# main_schematic.net
KiCad netlist of a schematic drawn in Altium Designer
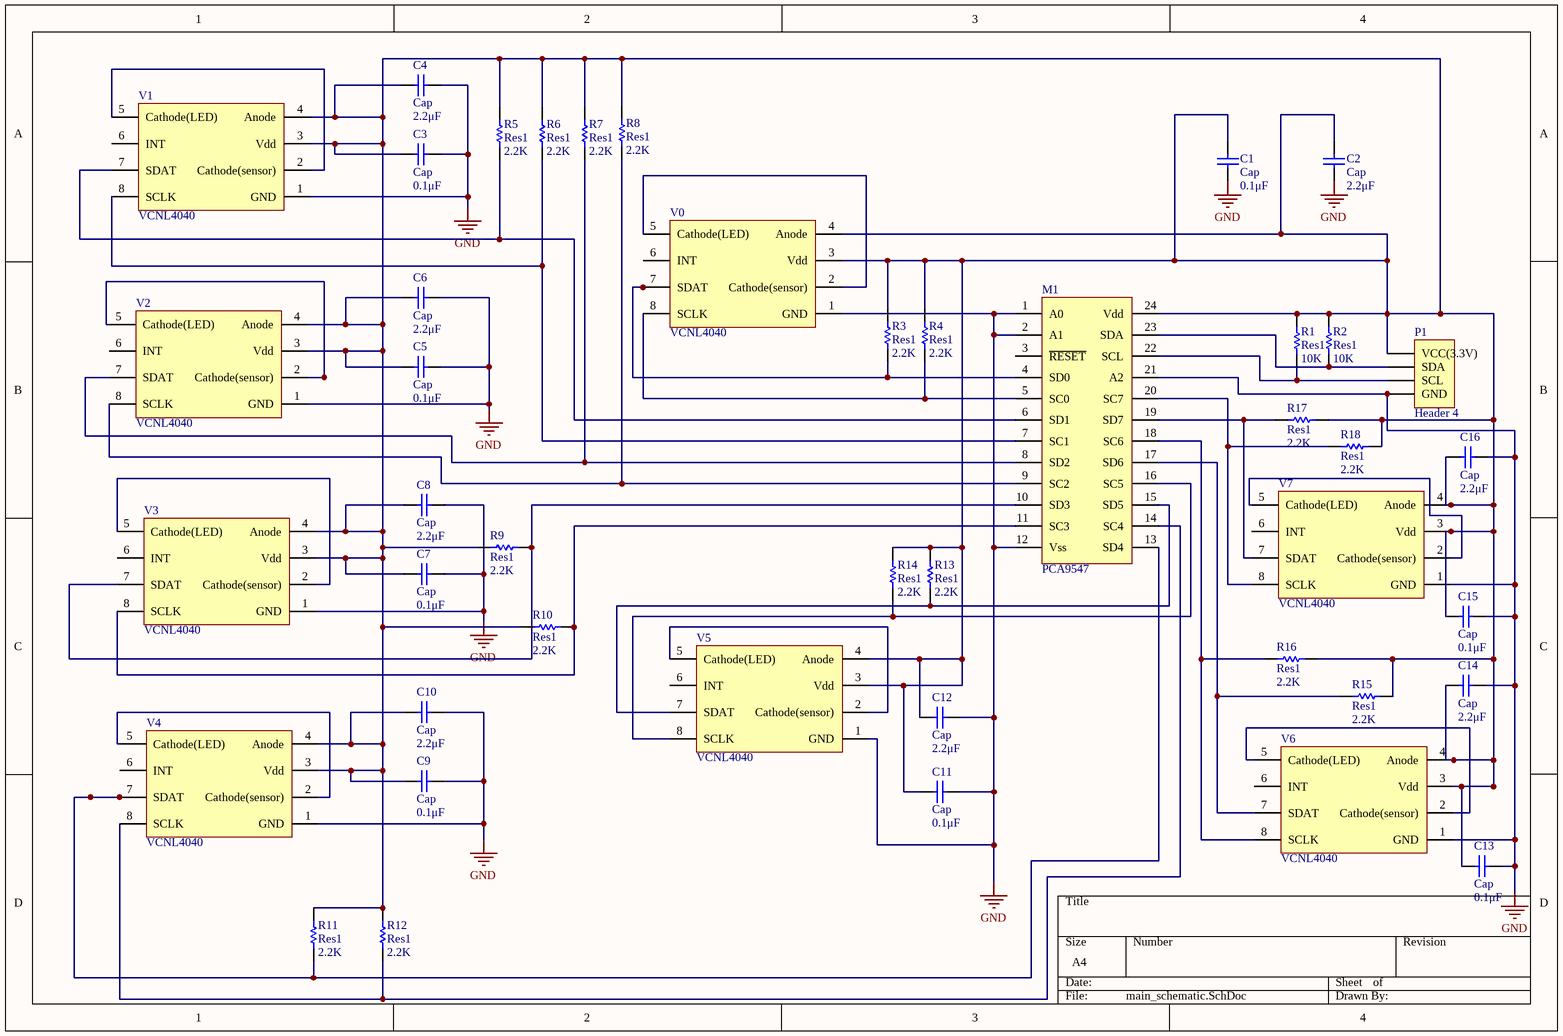
[diagram p0: main_schematic.SchDoc]

(export (version "E")
  (design (tool "Eeschema 10.0.6"))
  (components
    (comp (ref "C1")
      (value "Cap")
      (footprint "1608[0603]")
      (description "Capacitor")
      (fields (field (name "ALTIUM_VALUE") "0.1μF") (field (name "PUBLISHER") "Altium Limited"))
      (libsource (lib "Miscellaneous Devices") (part "Cap"))
    )
    (comp (ref "C2")
      (value "Cap")
      (footprint "1608[0603]")
      (description "Capacitor")
      (fields (field (name "ALTIUM_VALUE") "2.2μF") (field (name "PUBLISHER") "Altium Limited"))
      (libsource (lib "Miscellaneous Devices") (part "Cap"))
    )
    (comp (ref "C3")
      (value "Cap")
      (footprint "1608[0603]")
      (description "Capacitor")
      (fields (field (name "ALTIUM_VALUE") "0.1μF") (field (name "PUBLISHER") "Altium Limited"))
      (libsource (lib "Miscellaneous Devices") (part "Cap"))
    )
    (comp (ref "C4")
      (value "Cap")
      (footprint "1608[0603]")
      (description "Capacitor")
      (fields (field (name "ALTIUM_VALUE") "2.2μF") (field (name "PUBLISHER") "Altium Limited"))
      (libsource (lib "Miscellaneous Devices") (part "Cap"))
    )
    (comp (ref "C5")
      (value "Cap")
      (footprint "1608[0603]")
      (description "Capacitor")
      (fields (field (name "ALTIUM_VALUE") "0.1μF") (field (name "PUBLISHER") "Altium Limited"))
      (libsource (lib "Miscellaneous Devices") (part "Cap"))
    )
    (comp (ref "C6")
      (value "Cap")
      (footprint "1608[0603]")
      (description "Capacitor")
      (fields (field (name "ALTIUM_VALUE") "2.2μF") (field (name "PUBLISHER") "Altium Limited"))
      (libsource (lib "Miscellaneous Devices") (part "Cap"))
    )
    (comp (ref "C7")
      (value "Cap")
      (footprint "1608[0603]")
      (description "Capacitor")
      (fields (field (name "ALTIUM_VALUE") "0.1μF") (field (name "PUBLISHER") "Altium Limited"))
      (libsource (lib "Miscellaneous Devices") (part "Cap"))
    )
    (comp (ref "C8")
      (value "Cap")
      (footprint "1608[0603]")
      (description "Capacitor")
      (fields (field (name "ALTIUM_VALUE") "2.2μF") (field (name "PUBLISHER") "Altium Limited"))
      (libsource (lib "Miscellaneous Devices") (part "Cap"))
    )
    (comp (ref "C9")
      (value "Cap")
      (footprint "1608[0603]")
      (description "Capacitor")
      (fields (field (name "ALTIUM_VALUE") "0.1μF") (field (name "PUBLISHER") "Altium Limited"))
      (libsource (lib "Miscellaneous Devices") (part "Cap"))
    )
    (comp (ref "C10")
      (value "Cap")
      (footprint "1608[0603]")
      (description "Capacitor")
      (fields (field (name "ALTIUM_VALUE") "2.2μF") (field (name "PUBLISHER") "Altium Limited"))
      (libsource (lib "Miscellaneous Devices") (part "Cap"))
    )
    (comp (ref "C11")
      (value "Cap")
      (footprint "1608[0603]")
      (description "Capacitor")
      (fields (field (name "ALTIUM_VALUE") "0.1μF") (field (name "PUBLISHER") "Altium Limited"))
      (libsource (lib "Miscellaneous Devices") (part "Cap"))
    )
    (comp (ref "C12")
      (value "Cap")
      (footprint "1608[0603]")
      (description "Capacitor")
      (fields (field (name "ALTIUM_VALUE") "2.2μF") (field (name "PUBLISHER") "Altium Limited"))
      (libsource (lib "Miscellaneous Devices") (part "Cap"))
    )
    (comp (ref "C13")
      (value "Cap")
      (footprint "1608[0603]")
      (description "Capacitor")
      (fields (field (name "ALTIUM_VALUE") "0.1μF") (field (name "PUBLISHER") "Altium Limited"))
      (libsource (lib "Miscellaneous Devices") (part "Cap"))
    )
    (comp (ref "C14")
      (value "Cap")
      (footprint "1608[0603]")
      (description "Capacitor")
      (fields (field (name "ALTIUM_VALUE") "2.2μF") (field (name "PUBLISHER") "Altium Limited"))
      (libsource (lib "Miscellaneous Devices") (part "Cap"))
    )
    (comp (ref "C15")
      (value "Cap")
      (footprint "1608[0603]")
      (description "Capacitor")
      (fields (field (name "ALTIUM_VALUE") "0.1μF") (field (name "PUBLISHER") "Altium Limited"))
      (libsource (lib "Miscellaneous Devices") (part "Cap"))
    )
    (comp (ref "C16")
      (value "Cap")
      (footprint "1608[0603]")
      (description "Capacitor")
      (fields (field (name "ALTIUM_VALUE") "2.2μF") (field (name "PUBLISHER") "Altium Limited"))
      (libsource (lib "Miscellaneous Devices") (part "Cap"))
    )
    (comp (ref "M1") (value "PCA9547") (footprint "TSSOP24") (libsource (lib "PCA9547") (part "PCA9547")))
    (comp (ref "P1")
      (value "Header 4")
      (footprint "HDR1X4")
      (description "Header, 4-Pin")
      (fields (field (name "PUBLISHER") "Altium Limited"))
      (libsource (lib "Miscellaneous Connectors") (part "Header 4"))
    )
    (comp (ref "R1")
      (value "Res1")
      (footprint "1608[0603]")
      (description "Resistor")
      (fields (field (name "ALTIUM_VALUE") "10K") (field (name "PUBLISHER") "Altium Limited"))
      (libsource (lib "Miscellaneous Devices") (part "Res1"))
    )
    (comp (ref "R2")
      (value "Res1")
      (footprint "1608[0603]")
      (description "Resistor")
      (fields (field (name "ALTIUM_VALUE") "10K") (field (name "PUBLISHER") "Altium Limited"))
      (libsource (lib "Miscellaneous Devices") (part "Res1"))
    )
    (comp (ref "R3")
      (value "Res1")
      (footprint "1608[0603]")
      (description "Resistor")
      (fields (field (name "ALTIUM_VALUE") "2.2K") (field (name "PUBLISHER") "Altium Limited"))
      (libsource (lib "Miscellaneous Devices") (part "Res1"))
    )
    (comp (ref "R4")
      (value "Res1")
      (footprint "1608[0603]")
      (description "Resistor")
      (fields (field (name "ALTIUM_VALUE") "2.2K") (field (name "PUBLISHER") "Altium Limited"))
      (libsource (lib "Miscellaneous Devices") (part "Res1"))
    )
    (comp (ref "R5")
      (value "Res1")
      (footprint "1608[0603]")
      (description "Resistor")
      (fields (field (name "ALTIUM_VALUE") "2.2K") (field (name "PUBLISHER") "Altium Limited"))
      (libsource (lib "Miscellaneous Devices") (part "Res1"))
    )
    (comp (ref "R6")
      (value "Res1")
      (footprint "1608[0603]")
      (description "Resistor")
      (fields (field (name "ALTIUM_VALUE") "2.2K") (field (name "PUBLISHER") "Altium Limited"))
      (libsource (lib "Miscellaneous Devices") (part "Res1"))
    )
    (comp (ref "R7")
      (value "Res1")
      (footprint "1608[0603]")
      (description "Resistor")
      (fields (field (name "ALTIUM_VALUE") "2.2K") (field (name "PUBLISHER") "Altium Limited"))
      (libsource (lib "Miscellaneous Devices") (part "Res1"))
    )
    (comp (ref "R8")
      (value "Res1")
      (footprint "1608[0603]")
      (description "Resistor")
      (fields (field (name "ALTIUM_VALUE") "2.2K") (field (name "PUBLISHER") "Altium Limited"))
      (libsource (lib "Miscellaneous Devices") (part "Res1"))
    )
    (comp (ref "R9")
      (value "Res1")
      (footprint "1608[0603]")
      (description "Resistor")
      (fields (field (name "ALTIUM_VALUE") "2.2K") (field (name "PUBLISHER") "Altium Limited"))
      (libsource (lib "Miscellaneous Devices") (part "Res1"))
    )
    (comp (ref "R10")
      (value "Res1")
      (footprint "1608[0603]")
      (description "Resistor")
      (fields (field (name "ALTIUM_VALUE") "2.2K") (field (name "PUBLISHER") "Altium Limited"))
      (libsource (lib "Miscellaneous Devices") (part "Res1"))
    )
    (comp (ref "R11")
      (value "Res1")
      (footprint "1608[0603]")
      (description "Resistor")
      (fields (field (name "ALTIUM_VALUE") "2.2K") (field (name "PUBLISHER") "Altium Limited"))
      (libsource (lib "Miscellaneous Devices") (part "Res1"))
    )
    (comp (ref "R12")
      (value "Res1")
      (footprint "1608[0603]")
      (description "Resistor")
      (fields (field (name "ALTIUM_VALUE") "2.2K") (field (name "PUBLISHER") "Altium Limited"))
      (libsource (lib "Miscellaneous Devices") (part "Res1"))
    )
    (comp (ref "R13")
      (value "Res1")
      (footprint "1608[0603]")
      (description "Resistor")
      (fields (field (name "ALTIUM_VALUE") "2.2K") (field (name "PUBLISHER") "Altium Limited"))
      (libsource (lib "Miscellaneous Devices") (part "Res1"))
    )
    (comp (ref "R14")
      (value "Res1")
      (footprint "1608[0603]")
      (description "Resistor")
      (fields (field (name "ALTIUM_VALUE") "2.2K") (field (name "PUBLISHER") "Altium Limited"))
      (libsource (lib "Miscellaneous Devices") (part "Res1"))
    )
    (comp (ref "R15")
      (value "Res1")
      (footprint "1608[0603]")
      (description "Resistor")
      (fields (field (name "ALTIUM_VALUE") "2.2K") (field (name "PUBLISHER") "Altium Limited"))
      (libsource (lib "Miscellaneous Devices") (part "Res1"))
    )
    (comp (ref "R16")
      (value "Res1")
      (footprint "1608[0603]")
      (description "Resistor")
      (fields (field (name "ALTIUM_VALUE") "2.2K") (field (name "PUBLISHER") "Altium Limited"))
      (libsource (lib "Miscellaneous Devices") (part "Res1"))
    )
    (comp (ref "R17")
      (value "Res1")
      (footprint "1608[0603]")
      (description "Resistor")
      (fields (field (name "ALTIUM_VALUE") "2.2K") (field (name "PUBLISHER") "Altium Limited"))
      (libsource (lib "Miscellaneous Devices") (part "Res1"))
    )
    (comp (ref "R18")
      (value "Res1")
      (footprint "1608[0603]")
      (description "Resistor")
      (fields (field (name "ALTIUM_VALUE") "2.2K") (field (name "PUBLISHER") "Altium Limited"))
      (libsource (lib "Miscellaneous Devices") (part "Res1"))
    )
    (comp (ref "V0") (value "VCNL4040") (footprint "SOP8") (libsource (lib "VCNL4040") (part "Component_1")))
    (comp (ref "V1") (value "VCNL4040") (footprint "SOP8") (libsource (lib "VCNL4040") (part "Component_1")))
    (comp (ref "V2") (value "VCNL4040") (footprint "SOP8") (libsource (lib "VCNL4040") (part "Component_1")))
    (comp (ref "V3") (value "VCNL4040") (footprint "SOP8") (libsource (lib "VCNL4040") (part "Component_1")))
    (comp (ref "V4") (value "VCNL4040") (footprint "SOP8") (libsource (lib "VCNL4040") (part "Component_1")))
    (comp (ref "V5") (value "VCNL4040") (footprint "SOP8") (libsource (lib "VCNL4040") (part "Component_1")))
    (comp (ref "V6") (value "VCNL4040") (footprint "SOP8") (libsource (lib "VCNL4040") (part "Component_1")))
    (comp (ref "V7") (value "VCNL4040") (footprint "SOP8") (libsource (lib "VCNL4040") (part "Component_1")))
  )
  (nets
    (net (code "1") (name "GND") (class "Default")
      (node (ref "C1") (pin "1") (pinfunction "1_1") (pintype "passive"))
      (node (ref "C10") (pin "1") (pinfunction "1_1") (pintype "passive"))
      (node (ref "C11") (pin "1") (pinfunction "1_1") (pintype "passive"))
      (node (ref "C12") (pin "1") (pinfunction "1_1") (pintype "passive"))
      (node (ref "C13") (pin "1") (pinfunction "1_1") (pintype "passive"))
      (node (ref "C14") (pin "1") (pinfunction "1_1") (pintype "passive"))
      (node (ref "C15") (pin "1") (pinfunction "1_1") (pintype "passive"))
      (node (ref "C16") (pin "1") (pinfunction "1_1") (pintype "passive"))
      (node (ref "C2") (pin "1") (pinfunction "1_1") (pintype "passive"))
      (node (ref "C3") (pin "1") (pinfunction "1_1") (pintype "passive"))
      (node (ref "C4") (pin "1") (pinfunction "1_1") (pintype "passive"))
      (node (ref "C5") (pin "1") (pinfunction "1_1") (pintype "passive"))
      (node (ref "C6") (pin "1") (pinfunction "1_1") (pintype "passive"))
      (node (ref "C7") (pin "1") (pinfunction "1_1") (pintype "passive"))
      (node (ref "C8") (pin "1") (pinfunction "1_1") (pintype "passive"))
      (node (ref "C9") (pin "1") (pinfunction "1_1") (pintype "passive"))
      (node (ref "M1") (pin "1") (pinfunction "A0_1") (pintype "passive"))
      (node (ref "M1") (pin "12") (pinfunction "Vss_12") (pintype "passive"))
      (node (ref "M1") (pin "2") (pinfunction "A1_2") (pintype "passive"))
      (node (ref "M1") (pin "21") (pinfunction "A2_21") (pintype "passive"))
      (node (ref "P1") (pin "4") (pinfunction "GND_4") (pintype "power_in"))
      (node (ref "V0") (pin "1") (pinfunction "GND_1") (pintype "passive"))
      (node (ref "V1") (pin "1") (pinfunction "GND_1") (pintype "passive"))
      (node (ref "V2") (pin "1") (pinfunction "GND_1") (pintype "passive"))
      (node (ref "V3") (pin "1") (pinfunction "GND_1") (pintype "passive"))
      (node (ref "V4") (pin "1") (pinfunction "GND_1") (pintype "passive"))
      (node (ref "V5") (pin "1") (pinfunction "GND_1") (pintype "passive"))
      (node (ref "V6") (pin "1") (pinfunction "GND_1") (pintype "passive"))
      (node (ref "V7") (pin "1") (pinfunction "GND_1") (pintype "passive"))
    )
    (net (code "2") (name "Net-(M1-SC0)") (class "Default")
      (node (ref "M1") (pin "5") (pinfunction "SC0_5") (pintype "passive"))
      (node (ref "R4") (pin "1") (pinfunction "1_1") (pintype "passive"))
      (node (ref "V0") (pin "8") (pinfunction "SCLK_8") (pintype "passive"))
    )
    (net (code "3") (name "Net-(M1-SC1)") (class "Default")
      (node (ref "M1") (pin "7") (pinfunction "SC1_7") (pintype "passive"))
      (node (ref "R6") (pin "1") (pinfunction "1_1") (pintype "passive"))
      (node (ref "V1") (pin "8") (pinfunction "SCLK_8") (pintype "passive"))
    )
    (net (code "4") (name "Net-(M1-SC2)") (class "Default")
      (node (ref "M1") (pin "9") (pinfunction "SC2_9") (pintype "passive"))
      (node (ref "R8") (pin "1") (pinfunction "1_1") (pintype "passive"))
      (node (ref "V2") (pin "8") (pinfunction "SCLK_8") (pintype "passive"))
    )
    (net (code "5") (name "Net-(M1-SC3)") (class "Default")
      (node (ref "M1") (pin "11") (pinfunction "SC3_11") (pintype "passive"))
      (node (ref "R10") (pin "1") (pinfunction "1_1") (pintype "passive"))
      (node (ref "V3") (pin "8") (pinfunction "SCLK_8") (pintype "passive"))
    )
    (net (code "6") (name "Net-(M1-SC4)") (class "Default")
      (node (ref "M1") (pin "14") (pinfunction "SC4_14") (pintype "passive"))
      (node (ref "R12") (pin "2") (pinfunction "2_2") (pintype "passive"))
      (node (ref "V4") (pin "8") (pinfunction "SCLK_8") (pintype "passive"))
    )
    (net (code "7") (name "Net-(M1-SC5)") (class "Default")
      (node (ref "M1") (pin "16") (pinfunction "SC5_16") (pintype "passive"))
      (node (ref "R14") (pin "1") (pinfunction "1_1") (pintype "passive"))
      (node (ref "V5") (pin "8") (pinfunction "SCLK_8") (pintype "passive"))
    )
    (net (code "8") (name "Net-(M1-SC6)") (class "Default")
      (node (ref "M1") (pin "18") (pinfunction "SC6_18") (pintype "passive"))
      (node (ref "R16") (pin "2") (pinfunction "2_2") (pintype "passive"))
      (node (ref "V6") (pin "8") (pinfunction "SCLK_8") (pintype "passive"))
    )
    (net (code "9") (name "Net-(M1-SC7)") (class "Default")
      (node (ref "M1") (pin "20") (pinfunction "SC7_20") (pintype "passive"))
      (node (ref "R18") (pin "2") (pinfunction "2_2") (pintype "passive"))
      (node (ref "V7") (pin "8") (pinfunction "SCLK_8") (pintype "passive"))
    )
    (net (code "10") (name "Net-(M1-SCL)") (class "Default")
      (node (ref "M1") (pin "22") (pinfunction "SCL_22") (pintype "passive"))
      (node (ref "P1") (pin "3") (pinfunction "SCL_3") (pintype "passive"))
      (node (ref "R1") (pin "1") (pinfunction "1_1") (pintype "passive"))
    )
    (net (code "11") (name "Net-(M1-SD0)") (class "Default")
      (node (ref "M1") (pin "4") (pinfunction "SD0_4") (pintype "passive"))
      (node (ref "R3") (pin "1") (pinfunction "1_1") (pintype "passive"))
      (node (ref "V0") (pin "7") (pinfunction "SDAT_7") (pintype "passive"))
    )
    (net (code "12") (name "Net-(M1-SD1)") (class "Default")
      (node (ref "M1") (pin "6") (pinfunction "SD1_6") (pintype "passive"))
      (node (ref "R5") (pin "1") (pinfunction "1_1") (pintype "passive"))
      (node (ref "V1") (pin "7") (pinfunction "SDAT_7") (pintype "passive"))
    )
    (net (code "13") (name "Net-(M1-SD2)") (class "Default")
      (node (ref "M1") (pin "8") (pinfunction "SD2_8") (pintype "passive"))
      (node (ref "R7") (pin "1") (pinfunction "1_1") (pintype "passive"))
      (node (ref "V2") (pin "7") (pinfunction "SDAT_7") (pintype "passive"))
    )
    (net (code "14") (name "Net-(M1-SD3)") (class "Default")
      (node (ref "M1") (pin "10") (pinfunction "SD3_10") (pintype "passive"))
      (node (ref "R9") (pin "1") (pinfunction "1_1") (pintype "passive"))
      (node (ref "V3") (pin "7") (pinfunction "SDAT_7") (pintype "passive"))
    )
    (net (code "15") (name "Net-(M1-SD4)") (class "Default")
      (node (ref "M1") (pin "13") (pinfunction "SD4_13") (pintype "passive"))
      (node (ref "R11") (pin "2") (pinfunction "2_2") (pintype "passive"))
      (node (ref "V4") (pin "7") (pinfunction "SDAT_7") (pintype "passive"))
    )
    (net (code "16") (name "Net-(M1-SD5)") (class "Default")
      (node (ref "M1") (pin "15") (pinfunction "SD5_15") (pintype "passive"))
      (node (ref "R13") (pin "1") (pinfunction "1_1") (pintype "passive"))
      (node (ref "V5") (pin "7") (pinfunction "SDAT_7") (pintype "passive"))
    )
    (net (code "17") (name "Net-(M1-SD6)") (class "Default")
      (node (ref "M1") (pin "17") (pinfunction "SD6_17") (pintype "passive"))
      (node (ref "R15") (pin "2") (pinfunction "2_2") (pintype "passive"))
      (node (ref "V6") (pin "7") (pinfunction "SDAT_7") (pintype "passive"))
    )
    (net (code "18") (name "Net-(M1-SD7)") (class "Default")
      (node (ref "M1") (pin "19") (pinfunction "SD7_19") (pintype "passive"))
      (node (ref "R17") (pin "2") (pinfunction "2_2") (pintype "passive"))
      (node (ref "V7") (pin "7") (pinfunction "SDAT_7") (pintype "passive"))
    )
    (net (code "19") (name "Net-(M1-SDA)") (class "Default")
      (node (ref "M1") (pin "23") (pinfunction "SDA_23") (pintype "passive"))
      (node (ref "P1") (pin "2") (pinfunction "SDA_2") (pintype "passive"))
      (node (ref "R2") (pin "1") (pinfunction "1_1") (pintype "passive"))
    )
    (net (code "20") (name "Net-(M1-Vdd)") (class "Default")
      (node (ref "C1") (pin "2") (pinfunction "2_2") (pintype "passive"))
      (node (ref "C10") (pin "2") (pinfunction "2_2") (pintype "passive"))
      (node (ref "C11") (pin "2") (pinfunction "2_2") (pintype "passive"))
      (node (ref "C12") (pin "2") (pinfunction "2_2") (pintype "passive"))
      (node (ref "C13") (pin "2") (pinfunction "2_2") (pintype "passive"))
      (node (ref "C14") (pin "2") (pinfunction "2_2") (pintype "passive"))
      (node (ref "C15") (pin "2") (pinfunction "2_2") (pintype "passive"))
      (node (ref "C16") (pin "2") (pinfunction "2_2") (pintype "passive"))
      (node (ref "C2") (pin "2") (pinfunction "2_2") (pintype "passive"))
      (node (ref "C3") (pin "2") (pinfunction "2_2") (pintype "passive"))
      (node (ref "C4") (pin "2") (pinfunction "2_2") (pintype "passive"))
      (node (ref "C5") (pin "2") (pinfunction "2_2") (pintype "passive"))
      (node (ref "C6") (pin "2") (pinfunction "2_2") (pintype "passive"))
      (node (ref "C7") (pin "2") (pinfunction "2_2") (pintype "passive"))
      (node (ref "C8") (pin "2") (pinfunction "2_2") (pintype "passive"))
      (node (ref "C9") (pin "2") (pinfunction "2_2") (pintype "passive"))
      (node (ref "M1") (pin "24") (pinfunction "Vdd_24") (pintype "passive"))
      (node (ref "P1") (pin "1") (pinfunction "VCC(3.3V)_1") (pintype "power_in"))
      (node (ref "R1") (pin "2") (pinfunction "2_2") (pintype "passive"))
      (node (ref "R10") (pin "2") (pinfunction "2_2") (pintype "passive"))
      (node (ref "R11") (pin "1") (pinfunction "1_1") (pintype "passive"))
      (node (ref "R12") (pin "1") (pinfunction "1_1") (pintype "passive"))
      (node (ref "R13") (pin "2") (pinfunction "2_2") (pintype "passive"))
      (node (ref "R14") (pin "2") (pinfunction "2_2") (pintype "passive"))
      (node (ref "R15") (pin "1") (pinfunction "1_1") (pintype "passive"))
      (node (ref "R16") (pin "1") (pinfunction "1_1") (pintype "passive"))
      (node (ref "R17") (pin "1") (pinfunction "1_1") (pintype "passive"))
      (node (ref "R18") (pin "1") (pinfunction "1_1") (pintype "passive"))
      (node (ref "R2") (pin "2") (pinfunction "2_2") (pintype "passive"))
      (node (ref "R3") (pin "2") (pinfunction "2_2") (pintype "passive"))
      (node (ref "R4") (pin "2") (pinfunction "2_2") (pintype "passive"))
      (node (ref "R5") (pin "2") (pinfunction "2_2") (pintype "passive"))
      (node (ref "R6") (pin "2") (pinfunction "2_2") (pintype "passive"))
      (node (ref "R7") (pin "2") (pinfunction "2_2") (pintype "passive"))
      (node (ref "R8") (pin "2") (pinfunction "2_2") (pintype "passive"))
      (node (ref "R9") (pin "2") (pinfunction "2_2") (pintype "passive"))
      (node (ref "V0") (pin "3") (pinfunction "Vdd_3") (pintype "passive"))
      (node (ref "V0") (pin "4") (pinfunction "Anode_4") (pintype "passive"))
      (node (ref "V1") (pin "3") (pinfunction "Vdd_3") (pintype "passive"))
      (node (ref "V1") (pin "4") (pinfunction "Anode_4") (pintype "passive"))
      (node (ref "V2") (pin "3") (pinfunction "Vdd_3") (pintype "passive"))
      (node (ref "V2") (pin "4") (pinfunction "Anode_4") (pintype "passive"))
      (node (ref "V3") (pin "3") (pinfunction "Vdd_3") (pintype "passive"))
      (node (ref "V3") (pin "4") (pinfunction "Anode_4") (pintype "passive"))
      (node (ref "V4") (pin "3") (pinfunction "Vdd_3") (pintype "passive"))
      (node (ref "V4") (pin "4") (pinfunction "Anode_4") (pintype "passive"))
      (node (ref "V5") (pin "3") (pinfunction "Vdd_3") (pintype "passive"))
      (node (ref "V5") (pin "4") (pinfunction "Anode_4") (pintype "passive"))
      (node (ref "V6") (pin "3") (pinfunction "Vdd_3") (pintype "passive"))
      (node (ref "V6") (pin "4") (pinfunction "Anode_4") (pintype "passive"))
      (node (ref "V7") (pin "3") (pinfunction "Vdd_3") (pintype "passive"))
      (node (ref "V7") (pin "4") (pinfunction "Anode_4") (pintype "passive"))
    )
    (net (code "21") (name "Net-(V0-Cathode(LED))") (class "Default")
      (node (ref "V0") (pin "2") (pinfunction "Cathode(sensor)_2") (pintype "passive"))
      (node (ref "V0") (pin "5") (pinfunction "Cathode(LED)_5") (pintype "passive"))
    )
    (net (code "22") (name "Net-(V1-Cathode(LED))") (class "Default")
      (node (ref "V1") (pin "2") (pinfunction "Cathode(sensor)_2") (pintype "passive"))
      (node (ref "V1") (pin "5") (pinfunction "Cathode(LED)_5") (pintype "passive"))
    )
    (net (code "23") (name "Net-(V2-Cathode(LED))") (class "Default")
      (node (ref "V2") (pin "2") (pinfunction "Cathode(sensor)_2") (pintype "passive"))
      (node (ref "V2") (pin "5") (pinfunction "Cathode(LED)_5") (pintype "passive"))
    )
    (net (code "24") (name "Net-(V3-Cathode(LED))") (class "Default")
      (node (ref "V3") (pin "2") (pinfunction "Cathode(sensor)_2") (pintype "passive"))
      (node (ref "V3") (pin "5") (pinfunction "Cathode(LED)_5") (pintype "passive"))
    )
    (net (code "25") (name "Net-(V4-Cathode(LED))") (class "Default")
      (node (ref "V4") (pin "2") (pinfunction "Cathode(sensor)_2") (pintype "passive"))
      (node (ref "V4") (pin "5") (pinfunction "Cathode(LED)_5") (pintype "passive"))
    )
    (net (code "26") (name "Net-(V5-Cathode(LED))") (class "Default")
      (node (ref "V5") (pin "2") (pinfunction "Cathode(sensor)_2") (pintype "passive"))
      (node (ref "V5") (pin "5") (pinfunction "Cathode(LED)_5") (pintype "passive"))
    )
    (net (code "27") (name "Net-(V6-Cathode(LED))") (class "Default")
      (node (ref "V6") (pin "2") (pinfunction "Cathode(sensor)_2") (pintype "passive"))
      (node (ref "V6") (pin "5") (pinfunction "Cathode(LED)_5") (pintype "passive"))
    )
    (net (code "28") (name "Net-(V7-Cathode(LED))") (class "Default")
      (node (ref "V7") (pin "2") (pinfunction "Cathode(sensor)_2") (pintype "passive"))
      (node (ref "V7") (pin "5") (pinfunction "Cathode(LED)_5") (pintype "passive"))
    )
    (net (code "29") (name "unconnected-(M1-~{RESET}-Pad3)") (class "Default")
      (node (ref "M1") (pin "3") (pinfunction "~{RESET}_3") (pintype "passive"))
    )
    (net (code "30") (name "unconnected-(V0-INT-Pad6)") (class "Default")
      (node (ref "V0") (pin "6") (pinfunction "INT_6") (pintype "passive"))
    )
    (net (code "31") (name "unconnected-(V1-INT-Pad6)") (class "Default")
      (node (ref "V1") (pin "6") (pinfunction "INT_6") (pintype "passive"))
    )
    (net (code "32") (name "unconnected-(V2-INT-Pad6)") (class "Default")
      (node (ref "V2") (pin "6") (pinfunction "INT_6") (pintype "passive"))
    )
    (net (code "33") (name "unconnected-(V3-INT-Pad6)") (class "Default")
      (node (ref "V3") (pin "6") (pinfunction "INT_6") (pintype "passive"))
    )
    (net (code "34") (name "unconnected-(V4-INT-Pad6)") (class "Default")
      (node (ref "V4") (pin "6") (pinfunction "INT_6") (pintype "passive"))
    )
    (net (code "35") (name "unconnected-(V5-INT-Pad6)") (class "Default")
      (node (ref "V5") (pin "6") (pinfunction "INT_6") (pintype "passive"))
    )
    (net (code "36") (name "unconnected-(V6-INT-Pad6)") (class "Default")
      (node (ref "V6") (pin "6") (pinfunction "INT_6") (pintype "passive"))
    )
    (net (code "37") (name "unconnected-(V7-INT-Pad6)") (class "Default")
      (node (ref "V7") (pin "6") (pinfunction "INT_6") (pintype "passive"))
    )
  )
)
